# Peak_Detector.net
KiCad netlist of a schematic drawn in Altium Designer
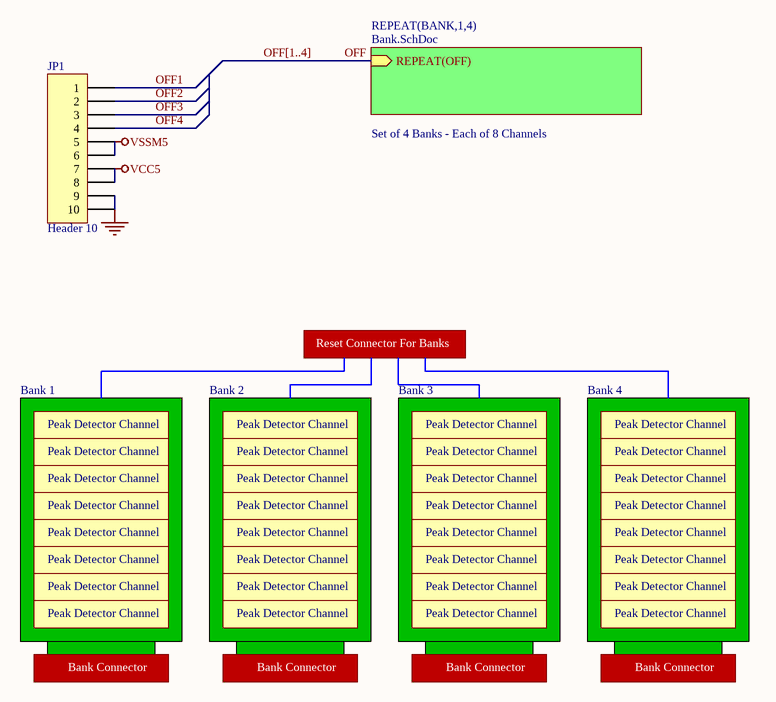
[diagram p0: Peak Detector.SchDoc]

(export (version "E")
  (design (tool "Eeschema 10.0.6"))
  (components
    (comp (ref "JP1")
      (value "Header 10")
      (footprint "HDR1X10")
      (description "Header, 10-Pin")
      (fields (field (name "MANUFACTURER") "Generic Components"))
      (libsource (lib "Miscellaneous Connectors") (part "Header 10"))
    )
  )
  (nets
    (net (code "2") (name "/OFF1") (class "Default")
      (node (ref "JP1") (pin "1") (pinfunction "1_1") (pintype "passive"))
    )
    (net (code "3") (name "/OFF2") (class "Default")
      (node (ref "JP1") (pin "2") (pinfunction "2_2") (pintype "passive"))
    )
    (net (code "4") (name "/OFF3") (class "Default")
      (node (ref "JP1") (pin "3") (pinfunction "3_3") (pintype "passive"))
    )
    (net (code "5") (name "/OFF4") (class "Default")
      (node (ref "JP1") (pin "4") (pinfunction "4_4") (pintype "passive"))
    )
    (net (code "7") (name "GND") (class "Default")
      (node (ref "JP1") (pin "10") (pinfunction "10_10") (pintype "passive"))
      (node (ref "JP1") (pin "9") (pinfunction "9_9") (pintype "passive"))
    )
    (net (code "8") (name "VCC5") (class "Default")
      (node (ref "JP1") (pin "7") (pinfunction "7_7") (pintype "passive"))
      (node (ref "JP1") (pin "8") (pinfunction "8_8") (pintype "passive"))
    )
    (net (code "9") (name "VSSM5") (class "Default")
      (node (ref "JP1") (pin "5") (pinfunction "5_5") (pintype "passive"))
      (node (ref "JP1") (pin "6") (pinfunction "6_6") (pintype "passive"))
    )
  )
)
